# StepperV2.net
KiCad netlist of a schematic drawn in Altium Designer
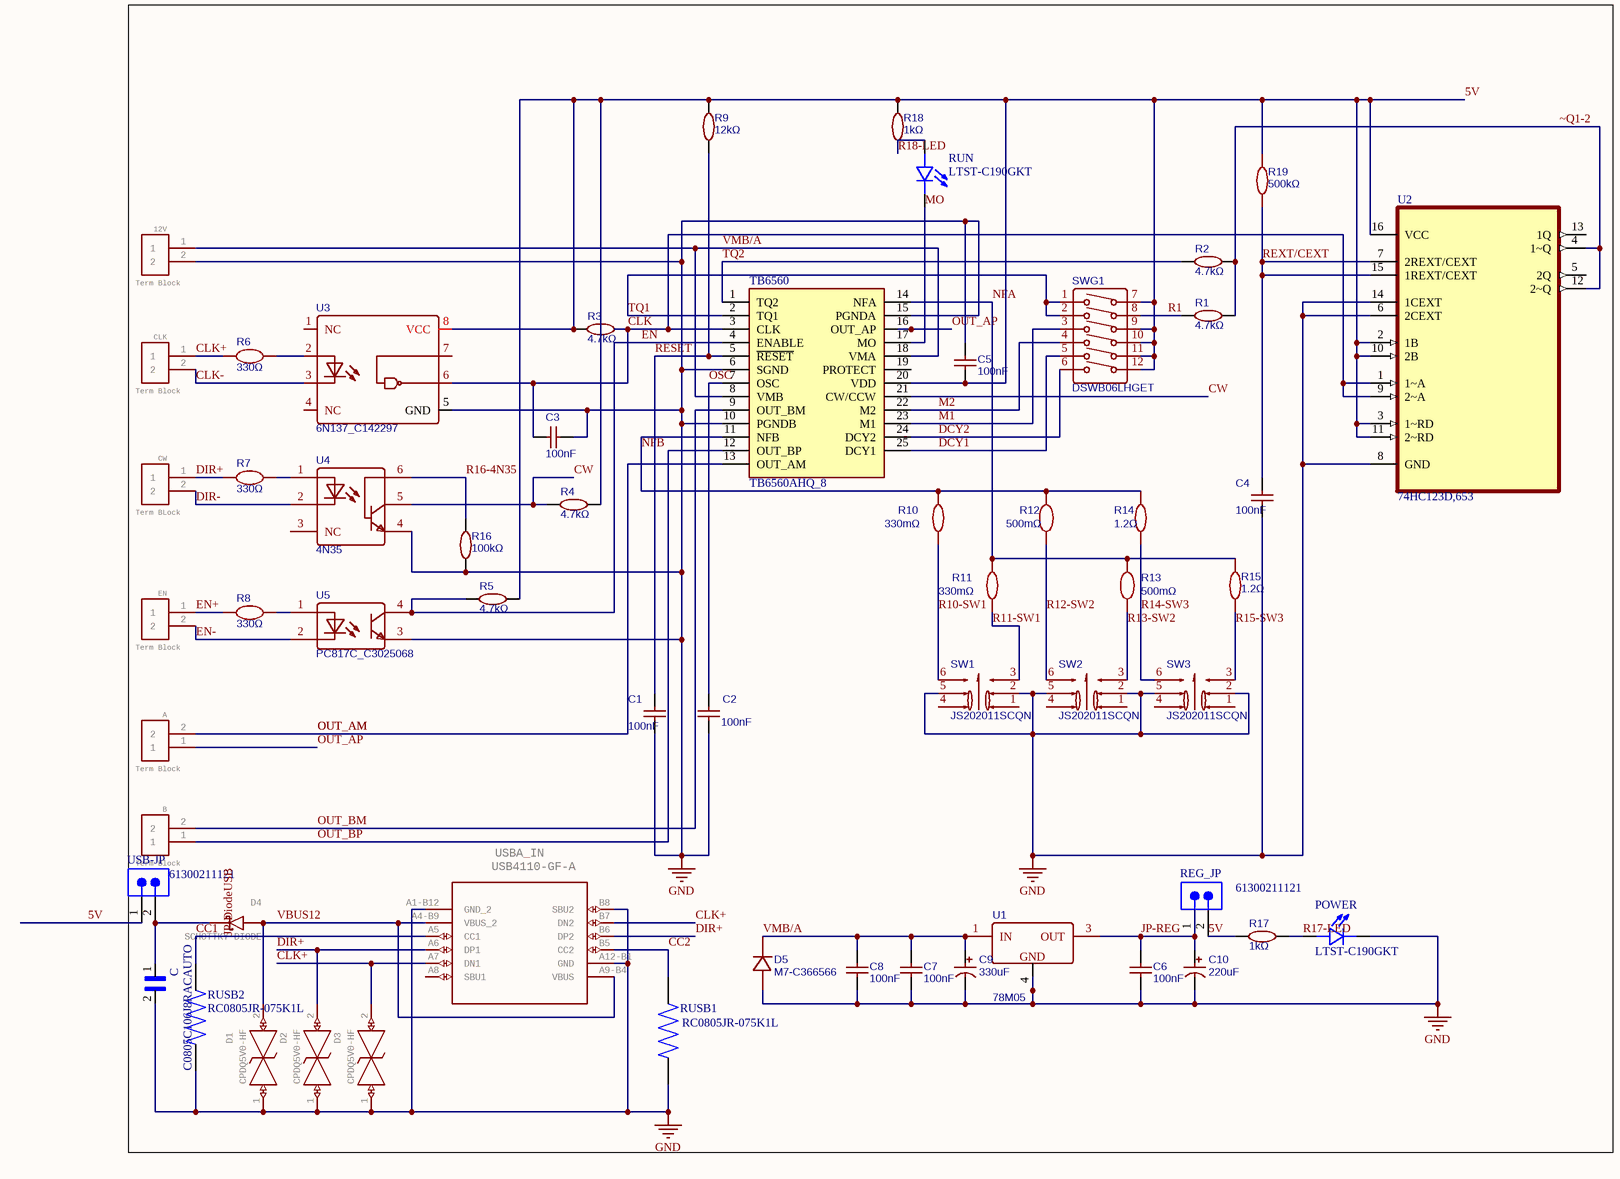
[diagram p0: StepperV2.SchDoc]

(export (version "E")
  (design (tool "Eeschema 10.0.6"))
  (components
    (comp (ref "12V")
      (value "Term Block")
      (footprint "TE_282837-2")
      (fields (field (name "MF") "TE Connectivity") (field (name "MP") "282837-2"))
      (libsource (lib "Terminal_Block2P") (part "282837-2"))
    )
    (comp (ref "A")
      (value "Term Block")
      (footprint "TE_282837-2")
      (fields (field (name "MF") "TE Connectivity") (field (name "MP") "282837-2"))
      (libsource (lib "") (part "282837-2_1"))
    )
    (comp (ref "B")
      (value "Term Block")
      (footprint "TE_282837-2")
      (fields (field (name "MF") "TE Connectivity") (field (name "MP") "282837-2"))
      (libsource (lib "Terminal_Block2P") (part "282837-2"))
    )
    (comp (ref "C")
      (value "C0805C106J8RACAUTO")
      (footprint "C0805C106J8RACAUTO.:CAPC2012X88N")
      (description "10ÂµF Â±5% 10V Ceramic Capacitor X7R 0805 _2012 Metric_")
      (fields (field (name "MF") "KEMET"))
      (libsource (lib "C0805C106J8RACAUTO") (part "C0805C106J8RACAUTO"))
    )
    (comp (ref "C1")
      (value "100nF")
      (footprint "C0805")
      (fields (field (name "MANUFACTURER") "FH(风华)") (field (name "MANUFACTURER PART") "0805B104J500NT"))
      (libsource (lib "0.1uFCAP") (part "100nF"))
    )
    (comp (ref "C2")
      (value "100nF")
      (footprint "C0805")
      (fields (field (name "MANUFACTURER") "FH(风华)") (field (name "MANUFACTURER PART") "0805B104J500NT"))
      (libsource (lib "0.1uFCAP") (part "100nF"))
    )
    (comp (ref "C3")
      (value "100nF")
      (footprint "C0805")
      (fields (field (name "MANUFACTURER") "FH(风华)") (field (name "MANUFACTURER PART") "0805B104J500NT"))
      (libsource (lib "0.1uFCAP") (part "100nF"))
    )
    (comp (ref "C4")
      (value "100nF")
      (footprint "C0805")
      (fields (field (name "MANUFACTURER") "FH(风华)") (field (name "MANUFACTURER PART") "0805B104J500NT"))
      (libsource (lib "0.1uFCAP") (part "100nF"))
    )
    (comp (ref "C5")
      (value "100nF")
      (footprint "C0805")
      (fields (field (name "MANUFACTURER") "FH(风华)") (field (name "MANUFACTURER PART") "0805B104J500NT"))
      (libsource (lib "0.1uFCAP") (part "100nF"))
    )
    (comp (ref "C6")
      (value "100nF")
      (footprint "C0805")
      (fields (field (name "MANUFACTURER") "FH(风华)") (field (name "MANUFACTURER PART") "0805B104J500NT"))
      (libsource (lib "0.1uFCAP") (part "100nF"))
    )
    (comp (ref "C7")
      (value "100nF")
      (footprint "C0805")
      (fields (field (name "MANUFACTURER") "FH(风华)") (field (name "MANUFACTURER PART") "0805B104J500NT"))
      (libsource (lib "0.1uFCAP") (part "100nF"))
    )
    (comp (ref "C8")
      (value "100nF")
      (footprint "C0805")
      (fields (field (name "MANUFACTURER") "FH(风华)") (field (name "MANUFACTURER PART") "0805B104J500NT"))
      (libsource (lib "0.1uFCAP") (part "100nF"))
    )
    (comp (ref "C9")
      (value "330uF")
      (footprint "CAP-TH_BD8.0-P3.50-D0.6-FD")
      (fields
        (field (name "MANUFACTURER") "CX(承兴)")
        (field (name "MANUFACTURER PART") "GR337M050F20RR0VL4FP0")
      )
      (libsource (lib "330uF_CAP") (part "330uF"))
    )
    (comp (ref "C10")
      (value "220uF")
      (footprint "CAP-TH_BD6.3-P2.50-D1.0-FD")
      (fields
        (field (name "MANUFACTURER") "CX(承兴)")
        (field (name "MANUFACTURER PART") "KM227M016E11RR0VH2FP0")
      )
      (libsource (lib "220uF_CAP") (part "220uF"))
    )
    (comp (ref "CLK")
      (value "Term Block")
      (footprint "TE_282837-2")
      (fields (field (name "MF") "TE Connectivity") (field (name "MP") "282837-2"))
      (libsource (lib "Terminal_Block2P") (part "282837-2"))
    )
    (comp (ref "CW")
      (value "Term BLock")
      (footprint "TE_282837-2")
      (fields (field (name "MF") "TE Connectivity") (field (name "MP") "282837-2"))
      (libsource (lib "Terminal_Block2P") (part "282837-2"))
    )
    (comp (ref "D1")
      (value "CPDQ5V0-HF")
      (footprint "MBTB-D-SOD-923F-IMP-0402")
      (fields (field (name "MF") "Comchip Technology"))
      (libsource (lib "CPDQ5V0-HF") (part "CPDQ5V0-HF"))
    )
    (comp (ref "D2")
      (value "CPDQ5V0-HF")
      (footprint "MBTB-D-SOD-923F-IMP-0402")
      (fields (field (name "MF") "Comchip Technology"))
      (libsource (lib "CPDQ5V0-HF") (part "CPDQ5V0-HF"))
    )
    (comp (ref "D3")
      (value "CPDQ5V0-HF")
      (footprint "MBTB-D-SOD-923F-IMP-0402")
      (fields (field (name "MF") "Comchip Technology"))
      (libsource (lib "CPDQ5V0-HF") (part "CPDQ5V0-HF"))
    )
    (comp (ref "D4")
      (value "SCHOTTKY DIODE")
      (footprint "SOD3715X145N")
      (fields (field (name "MF") "Diodes Inc.") (field (name "MP") "1N5819HW-7-F"))
      (libsource (lib "1N5819HW-7-F") (part "1N5819HW-7-F"))
    )
    (comp (ref "D5")
      (value "M7-C366566")
      (footprint "SMAF_L3.5-W2.6-LS4.7-RD")
      (fields
        (field (name "MANUFACTURER") "DOWO(东沃)")
        (field (name "MANUFACTURER PART") "M7")
        (field (name "CONTRIBUTOR") "LCSC")
      )
      (libsource (lib "M7") (part "M7-C366566"))
    )
    (comp (ref "EN")
      (value "Term Block")
      (footprint "TE_282837-2")
      (fields (field (name "MF") "TE Connectivity") (field (name "MP") "282837-2"))
      (libsource (lib "Terminal_Block2P") (part "282837-2"))
    )
    (comp (ref "POWER")
      (value "LTST-C190GKT")
      (footprint "LEDC1608X35N")
      (fields (field (name "MF") "{'manufacturer': u'Lite-On Inc.'}"))
      (libsource (lib "") (part "LTST-C190GKT_1"))
    )
    (comp (ref "R1")
      (value "4.7kΩ")
      (footprint "R0805")
      (fields (field (name "MANUFACTURER") "FH(风华)") (field (name "MANUFACTURER PART") "RS-05K472JT"))
      (libsource (lib "4_7KO") (part "4.7kΩ"))
    )
    (comp (ref "R2")
      (value "4.7kΩ")
      (footprint "R0805")
      (fields (field (name "MANUFACTURER") "FH(风华)") (field (name "MANUFACTURER PART") "RS-05K472JT"))
      (libsource (lib "4_7KO") (part "4.7kΩ"))
    )
    (comp (ref "R3")
      (value "4.7kΩ")
      (footprint "R0805")
      (fields (field (name "MANUFACTURER") "FH(风华)") (field (name "MANUFACTURER PART") "RS-05K472JT"))
      (libsource (lib "4_7KO") (part "4.7kΩ"))
    )
    (comp (ref "R4")
      (value "4.7kΩ")
      (footprint "R0805")
      (fields (field (name "MANUFACTURER") "FH(风华)") (field (name "MANUFACTURER PART") "RS-05K472JT"))
      (libsource (lib "4_7KO") (part "4.7kΩ"))
    )
    (comp (ref "R5")
      (value "4.7kΩ")
      (footprint "R0805")
      (fields (field (name "MANUFACTURER") "FH(风华)") (field (name "MANUFACTURER PART") "RS-05K472JT"))
      (libsource (lib "4_7KO") (part "4.7kΩ"))
    )
    (comp (ref "R6")
      (value "330Ω")
      (footprint "R0805")
      (fields
        (field (name "MANUFACTURER") "EVER OHMS(天二科技)")
        (field (name "MANUFACTURER PART") "CR0805J330RP05Z")
        (field (name "CONTRIBUTOR") "LCSC")
      )
      (libsource (lib "330OHM") (part "330Ω"))
    )
    (comp (ref "R7")
      (value "330Ω")
      (footprint "R0805")
      (fields
        (field (name "MANUFACTURER") "EVER OHMS(天二科技)")
        (field (name "MANUFACTURER PART") "CR0805J330RP05Z")
        (field (name "CONTRIBUTOR") "LCSC")
      )
      (libsource (lib "330OHM") (part "330Ω"))
    )
    (comp (ref "R8")
      (value "330Ω")
      (footprint "R0805")
      (fields
        (field (name "MANUFACTURER") "EVER OHMS(天二科技)")
        (field (name "MANUFACTURER PART") "CR0805J330RP05Z")
        (field (name "CONTRIBUTOR") "LCSC")
      )
      (libsource (lib "330OHM") (part "330Ω"))
    )
    (comp (ref "R9")
      (value "12kΩ")
      (footprint "R0805")
      (fields
        (field (name "MANUFACTURER") "UNI-ROYAL(厚声)")
        (field (name "MANUFACTURER PART") "0805W8J0123T5E")
      )
      (libsource (lib "12kOHM") (part "12kΩ"))
    )
    (comp (ref "R10")
      (value "330mΩ")
      (footprint "R2512")
      (fields
        (field (name "MANUFACTURER") "EVER OHMS(天二科技)")
        (field (name "MANUFACTURER PART") "CRH2512JR330E04Z")
        (field (name "CONTRIBUTOR") "LCSC")
      )
      (libsource (lib "0_33OHM") (part "330mΩ"))
    )
    (comp (ref "R11")
      (value "330mΩ")
      (footprint "R2512")
      (fields
        (field (name "MANUFACTURER") "EVER OHMS(天二科技)")
        (field (name "MANUFACTURER PART") "CRH2512JR330E04Z")
        (field (name "CONTRIBUTOR") "LCSC")
      )
      (libsource (lib "0_33OHM") (part "330mΩ"))
    )
    (comp (ref "R12")
      (value "500mΩ")
      (footprint "R2512")
      (fields
        (field (name "MANUFACTURER") "SEI(Stackpole Electronics Inc.)")
        (field (name "MANUFACTURER PART") "CSRN2512FKR500")
        (field (name "CONTRIBUTOR") "LCSC")
      )
      (libsource (lib "0_5OHM") (part "500mΩ"))
    )
    (comp (ref "R13")
      (value "500mΩ")
      (footprint "R2512")
      (fields
        (field (name "MANUFACTURER") "SEI(Stackpole Electronics Inc.)")
        (field (name "MANUFACTURER PART") "CSRN2512FKR500")
        (field (name "CONTRIBUTOR") "LCSC")
      )
      (libsource (lib "0_5OHM") (part "500mΩ"))
    )
    (comp (ref "R14")
      (value "1.2Ω")
      (footprint "R1210")
      (fields
        (field (name "MANUFACTURER") "EVER OHMS(天二科技)")
        (field (name "MANUFACTURER PART") "CR1210F1R20P05S")
        (field (name "CONTRIBUTOR") "LCSC")
      )
      (libsource (lib "1_2OHM") (part "1.2Ω"))
    )
    (comp (ref "R15")
      (value "1.2Ω")
      (footprint "R1210")
      (fields
        (field (name "MANUFACTURER") "EVER OHMS(天二科技)")
        (field (name "MANUFACTURER PART") "CR1210F1R20P05S")
        (field (name "CONTRIBUTOR") "LCSC")
      )
      (libsource (lib "1_2OHM") (part "1.2Ω"))
    )
    (comp (ref "R16")
      (value "100kΩ")
      (footprint "R0805")
      (fields (field (name "MANUFACTURER") "RALEC(旺诠)") (field (name "MANUFACTURER PART") "RTT05104JTP"))
      (libsource (lib "100KOHM") (part "100kΩ"))
    )
    (comp (ref "R17")
      (value "1kΩ")
      (footprint "R0805")
      (fields (field (name "MANUFACTURER") "YAGEO(国巨)") (field (name "MANUFACTURER PART") "RC0805JR-071KL"))
      (libsource (lib "1kOHM") (part "1kΩ"))
    )
    (comp (ref "R18")
      (value "1kΩ")
      (footprint "R0805")
      (fields (field (name "MANUFACTURER") "YAGEO(国巨)") (field (name "MANUFACTURER PART") "RC0805JR-071KL"))
      (libsource (lib "1kOHM") (part "1kΩ"))
    )
    (comp (ref "R19")
      (value "500kΩ")
      (footprint "R0805")
      (fields
        (field (name "MANUFACTURER") "Viking(光颉)")
        (field (name "MANUFACTURER PART") "AR05BTCW5003")
        (field (name "CONTRIBUTOR") "LCSC")
      )
      (libsource (lib "500KOHM") (part "500kΩ"))
    )
    (comp (ref "REG_JP")
      (value "61300211121")
      (footprint "61300211121")
      (libsource (lib "61300211121") (part "CMP-1712-00002-5"))
    )
    (comp (ref "RUN")
      (value "LTST-C190GKT")
      (footprint "LEDC1608X35N")
      (fields (field (name "MF") "{'manufacturer': u'Lite-On Inc.'}"))
      (libsource (lib "LTST-C190GKT") (part "LTST-C190GKT"))
    )
    (comp (ref "RUSB1")
      (value "RC0805JR-075K1L")
      (footprint "RC0805JR-075K1L:RESC2012X60N")
      (description "RC0805 5,1K 5% 0,125W")
      (libsource (lib "RC0805JR-075K1L") (part "RC0805JR-075K1L"))
    )
    (comp (ref "RUSB2")
      (value "RC0805JR-075K1L")
      (footprint "RC0805JR-075K1L:RESC2012X60N")
      (description "RC0805 5,1K 5% 0,125W")
      (libsource (lib "RC0805JR-075K1L") (part "RC0805JR-075K1L"))
    )
    (comp (ref "SW1")
      (value "JS202011SCQN")
      (footprint "SW-SMD_JS202011SCQN")
      (fields (field (name "MANUFACTURER") "C&K") (field (name "CONTRIBUTOR") "LCSC"))
      (libsource (lib "DPSP_Switch") (part "JS202011SCQN"))
    )
    (comp (ref "SW2")
      (value "JS202011SCQN")
      (footprint "SW-SMD_JS202011SCQN")
      (fields (field (name "MANUFACTURER") "C&K") (field (name "CONTRIBUTOR") "LCSC"))
      (libsource (lib "DPSP_Switch") (part "JS202011SCQN"))
    )
    (comp (ref "SW3")
      (value "JS202011SCQN")
      (footprint "SW-SMD_JS202011SCQN")
      (fields (field (name "MANUFACTURER") "C&K") (field (name "CONTRIBUTOR") "LCSC"))
      (libsource (lib "DPSP_Switch") (part "JS202011SCQN"))
    )
    (comp (ref "SWG1")
      (value "DSWB06LHGET")
      (footprint "SW-TH_DSWB06LHGET")
      (fields (field (name "MANUFACTURER") "YE") (field (name "CONTRIBUTOR") "LCSC"))
      (libsource (lib "DSWB06LHGET") (part "DSWB06LHGET"))
    )
    (comp (ref "TB6560")
      (value "TB6560AHQ_8")
      (footprint "TO127P530X3650X1770-25P")
      (description "Motor / Motion / Ignition Controllers & Drivers Stepping Motor Driver IC")
      (fields (field (name "MANUFACTURER_PART_NUMBER") "TB6560AHQ,8"))
      (libsource (lib "TB6560AHQ_8") (part "TB6560AHQ_8"))
    )
    (comp (ref "U1")
      (value "78M05")
      (footprint "TO-252-2_L6.5-W6.1-P4.58-LS10.0-TL")
      (fields (field (name "MANUFACTURER") "SHIKUES(时科)"))
      (libsource (lib "78M05") (part "78M05"))
    )
    (comp (ref "U2")
      (value "74HC123D,653")
      (footprint "SOIC127P600X175-16N")
      (description "Monostable Multivibrator 65ns 16-SO")
      (fields (field (name "MF") "Nexperia USA") (field (name "DIGI-KEY_PART_NUMBER") "1727-2778-1-ND"))
      (libsource (lib "74HC123D,653") (part "74HC123D,653"))
    )
    (comp (ref "U3")
      (value "6N137_C142297")
      (footprint "DIP-8_L9.8-W6.6-P2.54-LS7.6-BL")
      (fields
        (field (name "MANUFACTURER") "EVERLIGHT(亿光)")
        (field (name "MANUFACTURER PART") "6N137")
        (field (name "CONTRIBUTOR") "LCSC")
      )
      (libsource (lib "6N137") (part "6N137_C142297"))
    )
    (comp (ref "U4")
      (value "4N35")
      (footprint "DIP-6_L8.5-W6.4-P2.54-LS7.6-BL")
      (fields (field (name "MANUFACTURER") "EVERLIGHT(亿光)"))
      (libsource (lib "4N35") (part "4N35"))
    )
    (comp (ref "U5")
      (value "PC817C_C3025068")
      (footprint "DIP-4_L4.6-W6.5-P2.54-LS7.6-BL")
      (fields
        (field (name "MANUFACTURER") "GOODWORK(固得沃克)")
        (field (name "MANUFACTURER PART") "PC817C")
        (field (name "CONTRIBUTOR") "lcsc")
      )
      (libsource (lib "PC817C") (part "PC817C_C3025068"))
    )
    (comp (ref "USB-JP")
      (value "61300211121")
      (footprint "61300211121")
      (libsource (lib "61300211121") (part "CMP-1712-00002-5"))
    )
    (comp (ref "USBA_IN")
      (value "USB4110-GF-A")
      (footprint "USB4110-GF-A_GCT")
      (fields (field (name "COPYRIGHT") "Copyright (C) 2023 Ultra Librarian. All rights reserved."))
      (libsource (lib "USB4110-GF-A") (part "USB4110-GF-A"))
    )
  )
  (nets
    (net (code "1") (name "/5V") (class "Default")
      (node (ref "C5") (pin "1") (pinfunction "1_1") (pintype "passive"))
      (node (ref "R17") (pin "1") (pinfunction "1_1") (pintype "passive"))
      (node (ref "R18") (pin "2") (pinfunction "2_2") (pintype "passive"))
      (node (ref "R19") (pin "2") (pinfunction "2_2") (pintype "passive"))
      (node (ref "R3") (pin "1") (pinfunction "1_1") (pintype "passive"))
      (node (ref "R4") (pin "2") (pinfunction "2_2") (pintype "passive"))
      (node (ref "R5") (pin "2") (pinfunction "2_2") (pintype "passive"))
      (node (ref "R9") (pin "2") (pinfunction "2_2") (pintype "passive"))
      (node (ref "REG_JP") (pin "2") (pinfunction "2_2") (pintype "passive"))
      (node (ref "SWG1") (pin "10") (pinfunction "10_10") (pintype "passive"))
      (node (ref "SWG1") (pin "11") (pinfunction "11_11") (pintype "passive"))
      (node (ref "SWG1") (pin "12") (pinfunction "12_12") (pintype "passive"))
      (node (ref "SWG1") (pin "7") (pinfunction "7_7") (pintype "passive"))
      (node (ref "SWG1") (pin "9") (pinfunction "9_9") (pintype "passive"))
      (node (ref "TB6560") (pin "20") (pinfunction "VDD_20") (pintype "passive"))
      (node (ref "U2") (pin "10") (pinfunction "2B_10") (pintype "input"))
      (node (ref "U2") (pin "11") (pinfunction "2~RD_11") (pintype "input"))
      (node (ref "U2") (pin "16") (pinfunction "VCC_16") (pintype "power_in"))
      (node (ref "U2") (pin "2") (pinfunction "1B_2") (pintype "input"))
      (node (ref "U2") (pin "3") (pinfunction "1~RD_3") (pintype "input"))
      (node (ref "U3") (pin "8") (pinfunction "VCC_8") (pintype "passive"))
      (node (ref "USB-JP") (pin "1") (pinfunction "1_1") (pintype "passive"))
    )
    (net (code "2") (name "/CC1") (class "Default")
      (node (ref "RUSB2") (pin "2") (pinfunction "2_2") (pintype "passive"))
      (node (ref "USBA_IN") (pin "A5") (pinfunction "CC1_A5") (pintype "bidirectional"))
    )
    (net (code "3") (name "/CC2") (class "Default")
      (node (ref "RUSB1") (pin "2") (pinfunction "2_2") (pintype "passive"))
      (node (ref "USBA_IN") (pin "B5") (pinfunction "CC2_B5") (pintype "bidirectional"))
    )
    (net (code "4") (name "/CLK") (class "Default")
      (node (ref "C3") (pin "1") (pinfunction "1_1") (pintype "passive"))
      (node (ref "R3") (pin "2") (pinfunction "2_2") (pintype "passive"))
      (node (ref "TB6560") (pin "3") (pinfunction "CLK_3") (pintype "passive"))
      (node (ref "U2") (pin "1") (pinfunction "1~A_1") (pintype "input"))
      (node (ref "U2") (pin "9") (pinfunction "2~A_9") (pintype "input"))
      (node (ref "U3") (pin "6") (pinfunction "VOUT_6") (pintype "passive"))
    )
    (net (code "5") (name "/CLK+") (class "Default")
      (node (ref "CLK") (pin "1") (pinfunction "1_1") (pintype "passive"))
      (node (ref "D3") (pin "2") (pinfunction "A_2") (pintype "bidirectional"))
      (node (ref "R6") (pin "1") (pinfunction "1_1") (pintype "passive"))
      (node (ref "USBA_IN") (pin "A7") (pinfunction "DN1_A7") (pintype "bidirectional"))
      (node (ref "USBA_IN") (pin "B7") (pinfunction "DN2_B7") (pintype "bidirectional"))
    )
    (net (code "6") (name "/CLK-") (class "Default")
      (node (ref "CLK") (pin "2") (pinfunction "2_2") (pintype "passive"))
      (node (ref "U3") (pin "3") (pinfunction "CAT_3") (pintype "passive"))
    )
    (net (code "7") (name "/CW") (class "Default")
      (node (ref "R4") (pin "1") (pinfunction "1_1") (pintype "passive"))
      (node (ref "TB6560") (pin "21") (pinfunction "CW/CCW_21") (pintype "passive"))
      (node (ref "U4") (pin "5") (pinfunction "5_5") (pintype "passive"))
    )
    (net (code "8") (name "/DCY1") (class "Default")
      (node (ref "SWG1") (pin "5") (pinfunction "5_5") (pintype "passive"))
      (node (ref "TB6560") (pin "25") (pinfunction "DCY1_25") (pintype "passive"))
    )
    (net (code "9") (name "/DCY2") (class "Default")
      (node (ref "SWG1") (pin "6") (pinfunction "6_6") (pintype "passive"))
      (node (ref "TB6560") (pin "24") (pinfunction "DCY2_24") (pintype "passive"))
    )
    (net (code "10") (name "/DIR+") (class "Default")
      (node (ref "CW") (pin "1") (pinfunction "1_1") (pintype "passive"))
      (node (ref "D2") (pin "2") (pinfunction "A_2") (pintype "bidirectional"))
      (node (ref "R7") (pin "1") (pinfunction "1_1") (pintype "passive"))
      (node (ref "USBA_IN") (pin "A6") (pinfunction "DP1_A6") (pintype "bidirectional"))
      (node (ref "USBA_IN") (pin "B6") (pinfunction "DP2_B6") (pintype "bidirectional"))
    )
    (net (code "11") (name "/DIR-") (class "Default")
      (node (ref "CW") (pin "2") (pinfunction "2_2") (pintype "passive"))
      (node (ref "U4") (pin "2") (pinfunction "2_2") (pintype "passive"))
    )
    (net (code "12") (name "/EN") (class "Default")
      (node (ref "R5") (pin "1") (pinfunction "1_1") (pintype "passive"))
      (node (ref "TB6560") (pin "4") (pinfunction "ENABLE_4") (pintype "passive"))
      (node (ref "U5") (pin "4") (pinfunction "COL_4") (pintype "passive"))
    )
    (net (code "13") (name "/EN+") (class "Default")
      (node (ref "EN") (pin "1") (pinfunction "1_1") (pintype "passive"))
      (node (ref "R8") (pin "1") (pinfunction "1_1") (pintype "passive"))
    )
    (net (code "14") (name "/EN-") (class "Default")
      (node (ref "EN") (pin "2") (pinfunction "2_2") (pintype "passive"))
      (node (ref "U5") (pin "2") (pinfunction "CAT_2") (pintype "passive"))
    )
    (net (code "15") (name "/JP-REG") (class "Default")
      (node (ref "C10") (pin "1") (pinfunction "1_1") (pintype "passive"))
      (node (ref "C6") (pin "2") (pinfunction "2_2") (pintype "passive"))
      (node (ref "REG_JP") (pin "1") (pinfunction "1_1") (pintype "passive"))
      (node (ref "U1") (pin "3") (pinfunction "OUT_3") (pintype "passive"))
    )
    (net (code "16") (name "/M1") (class "Default")
      (node (ref "SWG1") (pin "3") (pinfunction "3_3") (pintype "passive"))
      (node (ref "TB6560") (pin "23") (pinfunction "M1_23") (pintype "passive"))
    )
    (net (code "17") (name "/M2") (class "Default")
      (node (ref "SWG1") (pin "4") (pinfunction "4_4") (pintype "passive"))
      (node (ref "TB6560") (pin "22") (pinfunction "M2_22") (pintype "passive"))
    )
    (net (code "18") (name "/MO") (class "Default")
      (node (ref "RUN") (pin "C") (pinfunction "C_C") (pintype "passive"))
      (node (ref "TB6560") (pin "17") (pinfunction "MO_17") (pintype "passive"))
    )
    (net (code "19") (name "/NFA") (class "Default")
      (node (ref "R11") (pin "2") (pinfunction "2_2") (pintype "passive"))
      (node (ref "R13") (pin "2") (pinfunction "2_2") (pintype "passive"))
      (node (ref "R15") (pin "2") (pinfunction "2_2") (pintype "passive"))
      (node (ref "TB6560") (pin "14") (pinfunction "NFA_14") (pintype "passive"))
    )
    (net (code "20") (name "/NFB") (class "Default")
      (node (ref "R10") (pin "2") (pinfunction "2_2") (pintype "passive"))
      (node (ref "R12") (pin "2") (pinfunction "2_2") (pintype "passive"))
      (node (ref "R14") (pin "2") (pinfunction "2_2") (pintype "passive"))
      (node (ref "TB6560") (pin "11") (pinfunction "NFB_11") (pintype "passive"))
    )
    (net (code "21") (name "/OSC") (class "Default")
      (node (ref "C2") (pin "1") (pinfunction "1_1") (pintype "passive"))
      (node (ref "TB6560") (pin "7") (pinfunction "OSC_7") (pintype "passive"))
    )
    (net (code "22") (name "/OUT_AM") (class "Default")
      (node (ref "A") (pin "2") (pinfunction "2_2") (pintype "passive"))
      (node (ref "TB6560") (pin "13") (pinfunction "OUT_AM_13") (pintype "passive"))
    )
    (net (code "23") (name "/OUT_AP") (class "Default")
      (node (ref "A") (pin "1") (pinfunction "1_1") (pintype "passive"))
      (node (ref "TB6560") (pin "16") (pinfunction "OUT_AP_16") (pintype "passive"))
    )
    (net (code "24") (name "/OUT_BM") (class "Default")
      (node (ref "B") (pin "2") (pinfunction "2_2") (pintype "passive"))
      (node (ref "TB6560") (pin "9") (pinfunction "OUT_BM_9") (pintype "passive"))
    )
    (net (code "25") (name "/OUT_BP") (class "Default")
      (node (ref "B") (pin "1") (pinfunction "1_1") (pintype "passive"))
      (node (ref "TB6560") (pin "12") (pinfunction "OUT_BP_12") (pintype "passive"))
    )
    (net (code "26") (name "/R1") (class "Default")
      (node (ref "R1") (pin "1") (pinfunction "1_1") (pintype "passive"))
      (node (ref "SWG1") (pin "8") (pinfunction "8_8") (pintype "passive"))
    )
    (net (code "27") (name "/R10-SW1") (class "Default")
      (node (ref "R10") (pin "1") (pinfunction "1_1") (pintype "passive"))
      (node (ref "SW1") (pin "6") (pinfunction "6_6") (pintype "passive"))
    )
    (net (code "28") (name "/R11-SW1") (class "Default")
      (node (ref "R11") (pin "1") (pinfunction "1_1") (pintype "passive"))
      (node (ref "SW1") (pin "3") (pinfunction "3_3") (pintype "passive"))
    )
    (net (code "29") (name "/R12-SW2") (class "Default")
      (node (ref "R12") (pin "1") (pinfunction "1_1") (pintype "passive"))
      (node (ref "SW2") (pin "6") (pinfunction "6_6") (pintype "passive"))
    )
    (net (code "30") (name "/R13-SW2") (class "Default")
      (node (ref "R13") (pin "1") (pinfunction "1_1") (pintype "passive"))
      (node (ref "SW2") (pin "3") (pinfunction "3_3") (pintype "passive"))
    )
    (net (code "31") (name "/R14-SW3") (class "Default")
      (node (ref "R14") (pin "1") (pinfunction "1_1") (pintype "passive"))
      (node (ref "SW3") (pin "6") (pinfunction "6_6") (pintype "passive"))
    )
    (net (code "32") (name "/R15-SW3") (class "Default")
      (node (ref "R15") (pin "1") (pinfunction "1_1") (pintype "passive"))
      (node (ref "SW3") (pin "3") (pinfunction "3_3") (pintype "passive"))
    )
    (net (code "33") (name "/R16-4N35") (class "Default")
      (node (ref "R16") (pin "2") (pinfunction "2_2") (pintype "passive"))
      (node (ref "U4") (pin "6") (pinfunction "6_6") (pintype "passive"))
    )
    (net (code "34") (name "/R17-LED") (class "Default")
      (node (ref "POWER") (pin "A") (pinfunction "A_A") (pintype "passive"))
      (node (ref "R17") (pin "2") (pinfunction "2_2") (pintype "passive"))
    )
    (net (code "35") (name "/R18-LED") (class "Default")
      (node (ref "R18") (pin "1") (pinfunction "1_1") (pintype "passive"))
      (node (ref "RUN") (pin "A") (pinfunction "A_A") (pintype "passive"))
    )
    (net (code "36") (name "/RESET") (class "Default")
      (node (ref "C1") (pin "2") (pinfunction "2_2") (pintype "passive"))
      (node (ref "R9") (pin "1") (pinfunction "1_1") (pintype "passive"))
      (node (ref "TB6560") (pin "5") (pinfunction "~{RESET}_5") (pintype "passive"))
    )
    (net (code "37") (name "/REXT{slash}CEXT") (class "Default")
      (node (ref "C4") (pin "2") (pinfunction "2_2") (pintype "passive"))
      (node (ref "R19") (pin "1") (pinfunction "1_1") (pintype "passive"))
      (node (ref "U2") (pin "15") (pinfunction "1REXT/CEXT_15") (pintype "passive"))
      (node (ref "U2") (pin "7") (pinfunction "2REXT/CEXT_7") (pintype "passive"))
    )
    (net (code "38") (name "/TQ1") (class "Default")
      (node (ref "SWG1") (pin "1") (pinfunction "1_1") (pintype "passive"))
      (node (ref "SWG1") (pin "2") (pinfunction "2_2") (pintype "passive"))
      (node (ref "TB6560") (pin "2") (pinfunction "TQ1_2") (pintype "passive"))
    )
    (net (code "39") (name "/TQ2") (class "Default")
      (node (ref "R2") (pin "1") (pinfunction "1_1") (pintype "passive"))
      (node (ref "TB6560") (pin "1") (pinfunction "TQ2_1") (pintype "passive"))
    )
    (net (code "40") (name "/VBUS12") (class "Default")
      (node (ref "D1") (pin "2") (pinfunction "A_2") (pintype "bidirectional"))
      (node (ref "D4") (pin "A") (pinfunction "A_A") (pintype "passive"))
      (node (ref "USBA_IN") (pin "A4-B9") (pinfunction "VBUS_2_A4-B9") (pintype "power_in"))
      (node (ref "USBA_IN") (pin "A9-B4") (pinfunction "VBUS_A9-B4") (pintype "power_in"))
    )
    (net (code "41") (name "/VMB{slash}A") (class "Default")
      (node (ref "12V") (pin "1") (pinfunction "1_1") (pintype "passive"))
      (node (ref "C7") (pin "2") (pinfunction "2_2") (pintype "passive"))
      (node (ref "C8") (pin "2") (pinfunction "2_2") (pintype "passive"))
      (node (ref "C9") (pin "1") (pinfunction "1_1") (pintype "passive"))
      (node (ref "D5") (pin "1") (pinfunction "C_1") (pintype "passive"))
      (node (ref "TB6560") (pin "18") (pinfunction "VMA_18") (pintype "passive"))
      (node (ref "TB6560") (pin "8") (pinfunction "VMB_8") (pintype "passive"))
      (node (ref "U1") (pin "1") (pinfunction "IN_1") (pintype "passive"))
    )
    (net (code "42") (name "/~Q1-2") (class "Default")
      (node (ref "R1") (pin "2") (pinfunction "2_2") (pintype "passive"))
      (node (ref "R2") (pin "2") (pinfunction "2_2") (pintype "passive"))
      (node (ref "U2") (pin "12") (pinfunction "2~Q_12") (pintype "output"))
      (node (ref "U2") (pin "4") (pinfunction "1~Q_4") (pintype "output"))
    )
    (net (code "43") (name "GND") (class "Default")
      (node (ref "12V") (pin "2") (pinfunction "2_2") (pintype "passive"))
      (node (ref "C") (pin "2") (pinfunction "2_2") (pintype "passive"))
      (node (ref "C1") (pin "1") (pinfunction "1_1") (pintype "passive"))
      (node (ref "C10") (pin "2") (pinfunction "2_2") (pintype "passive"))
      (node (ref "C2") (pin "2") (pinfunction "2_2") (pintype "passive"))
      (node (ref "C3") (pin "2") (pinfunction "2_2") (pintype "passive"))
      (node (ref "C4") (pin "1") (pinfunction "1_1") (pintype "passive"))
      (node (ref "C5") (pin "2") (pinfunction "2_2") (pintype "passive"))
      (node (ref "C6") (pin "1") (pinfunction "1_1") (pintype "passive"))
      (node (ref "C7") (pin "1") (pinfunction "1_1") (pintype "passive"))
      (node (ref "C8") (pin "1") (pinfunction "1_1") (pintype "passive"))
      (node (ref "C9") (pin "2") (pinfunction "2_2") (pintype "passive"))
      (node (ref "D1") (pin "1") (pinfunction "K_1") (pintype "bidirectional"))
      (node (ref "D2") (pin "1") (pinfunction "K_1") (pintype "bidirectional"))
      (node (ref "D3") (pin "1") (pinfunction "K_1") (pintype "bidirectional"))
      (node (ref "D5") (pin "2") (pinfunction "A_2") (pintype "passive"))
      (node (ref "POWER") (pin "C") (pinfunction "C_C") (pintype "passive"))
      (node (ref "R16") (pin "1") (pinfunction "1_1") (pintype "passive"))
      (node (ref "RUSB1") (pin "1") (pinfunction "1_1") (pintype "passive"))
      (node (ref "RUSB2") (pin "1") (pinfunction "1_1") (pintype "passive"))
      (node (ref "SW1") (pin "2") (pinfunction "2_2") (pintype "passive"))
      (node (ref "SW1") (pin "5") (pinfunction "5_5") (pintype "passive"))
      (node (ref "SW2") (pin "2") (pinfunction "2_2") (pintype "passive"))
      (node (ref "SW2") (pin "5") (pinfunction "5_5") (pintype "passive"))
      (node (ref "SW3") (pin "2") (pinfunction "2_2") (pintype "passive"))
      (node (ref "SW3") (pin "5") (pinfunction "5_5") (pintype "passive"))
      (node (ref "TB6560") (pin "10") (pinfunction "PGNDB_10") (pintype "passive"))
      (node (ref "TB6560") (pin "15") (pinfunction "PGNDA_15") (pintype "passive"))
      (node (ref "TB6560") (pin "6") (pinfunction "SGND_6") (pintype "passive"))
      (node (ref "U1") (pin "4") (pinfunction "GND_4") (pintype "passive"))
      (node (ref "U2") (pin "14") (pinfunction "1CEXT_14") (pintype "passive"))
      (node (ref "U2") (pin "6") (pinfunction "2CEXT_6") (pintype "passive"))
      (node (ref "U2") (pin "8") (pinfunction "GND_8") (pintype "passive"))
      (node (ref "U3") (pin "5") (pinfunction "GND_5") (pintype "passive"))
      (node (ref "U4") (pin "4") (pinfunction "4_4") (pintype "passive"))
      (node (ref "U5") (pin "3") (pinfunction "EM_3") (pintype "passive"))
      (node (ref "USBA_IN") (pin "A1-B12") (pinfunction "GND_2_A1-B12") (pintype "passive"))
      (node (ref "USBA_IN") (pin "A12-B1") (pinfunction "GND_A12-B1") (pintype "passive"))
      (node (ref "USBA_IN") (pin "B8") (pinfunction "SBU2_B8") (pintype "bidirectional"))
    )
    (net (code "44") (name "Net-(D4-K)") (class "Default")
      (node (ref "C") (pin "1") (pinfunction "1_1") (pintype "passive"))
      (node (ref "D4") (pin "C") (pinfunction "K_C") (pintype "passive"))
      (node (ref "USB-JP") (pin "2") (pinfunction "2_2") (pintype "passive"))
    )
    (net (code "45") (name "Net-(R7-Pad2)") (class "Default")
      (node (ref "R7") (pin "2") (pinfunction "2_2") (pintype "passive"))
      (node (ref "U4") (pin "1") (pinfunction "1_1") (pintype "passive"))
    )
    (net (code "46") (name "Net-(U3-AN)") (class "Default")
      (node (ref "R6") (pin "2") (pinfunction "2_2") (pintype "passive"))
      (node (ref "U3") (pin "2") (pinfunction "AN_2") (pintype "passive"))
    )
    (net (code "47") (name "Net-(U5-AN)") (class "Default")
      (node (ref "R8") (pin "2") (pinfunction "2_2") (pintype "passive"))
      (node (ref "U5") (pin "1") (pinfunction "AN_1") (pintype "passive"))
    )
    (net (code "48") (name "unconnected-(SW1-Pad1)") (class "Default")
      (node (ref "SW1") (pin "1") (pinfunction "1_1") (pintype "passive"))
    )
    (net (code "49") (name "unconnected-(SW1-Pad4)") (class "Default")
      (node (ref "SW1") (pin "4") (pinfunction "4_4") (pintype "passive"))
    )
    (net (code "50") (name "unconnected-(SW2-Pad1)") (class "Default")
      (node (ref "SW2") (pin "1") (pinfunction "1_1") (pintype "passive"))
    )
    (net (code "51") (name "unconnected-(SW2-Pad4)") (class "Default")
      (node (ref "SW2") (pin "4") (pinfunction "4_4") (pintype "passive"))
    )
    (net (code "52") (name "unconnected-(SW3-Pad1)") (class "Default")
      (node (ref "SW3") (pin "1") (pinfunction "1_1") (pintype "passive"))
    )
    (net (code "53") (name "unconnected-(SW3-Pad4)") (class "Default")
      (node (ref "SW3") (pin "4") (pinfunction "4_4") (pintype "passive"))
    )
    (net (code "54") (name "unconnected-(TB6560-PROTECT-Pad19)") (class "Default")
      (node (ref "TB6560") (pin "19") (pinfunction "PROTECT_19") (pintype "passive"))
    )
    (net (code "55") (name "unconnected-(U2-1Q-Pad13)") (class "Default")
      (node (ref "U2") (pin "13") (pinfunction "1Q_13") (pintype "output"))
    )
    (net (code "56") (name "unconnected-(U2-2Q-Pad5)") (class "Default")
      (node (ref "U2") (pin "5") (pinfunction "2Q_5") (pintype "output"))
    )
    (net (code "57") (name "unconnected-(U3-NC-Pad1)") (class "Default")
      (node (ref "U3") (pin "1") (pinfunction "NC_1") (pintype "passive"))
    )
    (net (code "58") (name "unconnected-(U3-NC-Pad4)") (class "Default")
      (node (ref "U3") (pin "4") (pinfunction "NC_4") (pintype "passive"))
    )
    (net (code "59") (name "unconnected-(U3-VE-Pad7)") (class "Default")
      (node (ref "U3") (pin "7") (pinfunction "VE_7") (pintype "passive"))
    )
    (net (code "60") (name "unconnected-(U4-NC-Pad3)") (class "Default")
      (node (ref "U4") (pin "3") (pinfunction "NC_3") (pintype "passive"))
    )
    (net (code "61") (name "unconnected-(USBA_IN-SBU1-PadA8)") (class "Default")
      (node (ref "USBA_IN") (pin "A8") (pinfunction "SBU1_A8") (pintype "bidirectional"))
    )
  )
)
